# pl2303HXD.net
KiCad netlist of a schematic drawn in Altium Designer
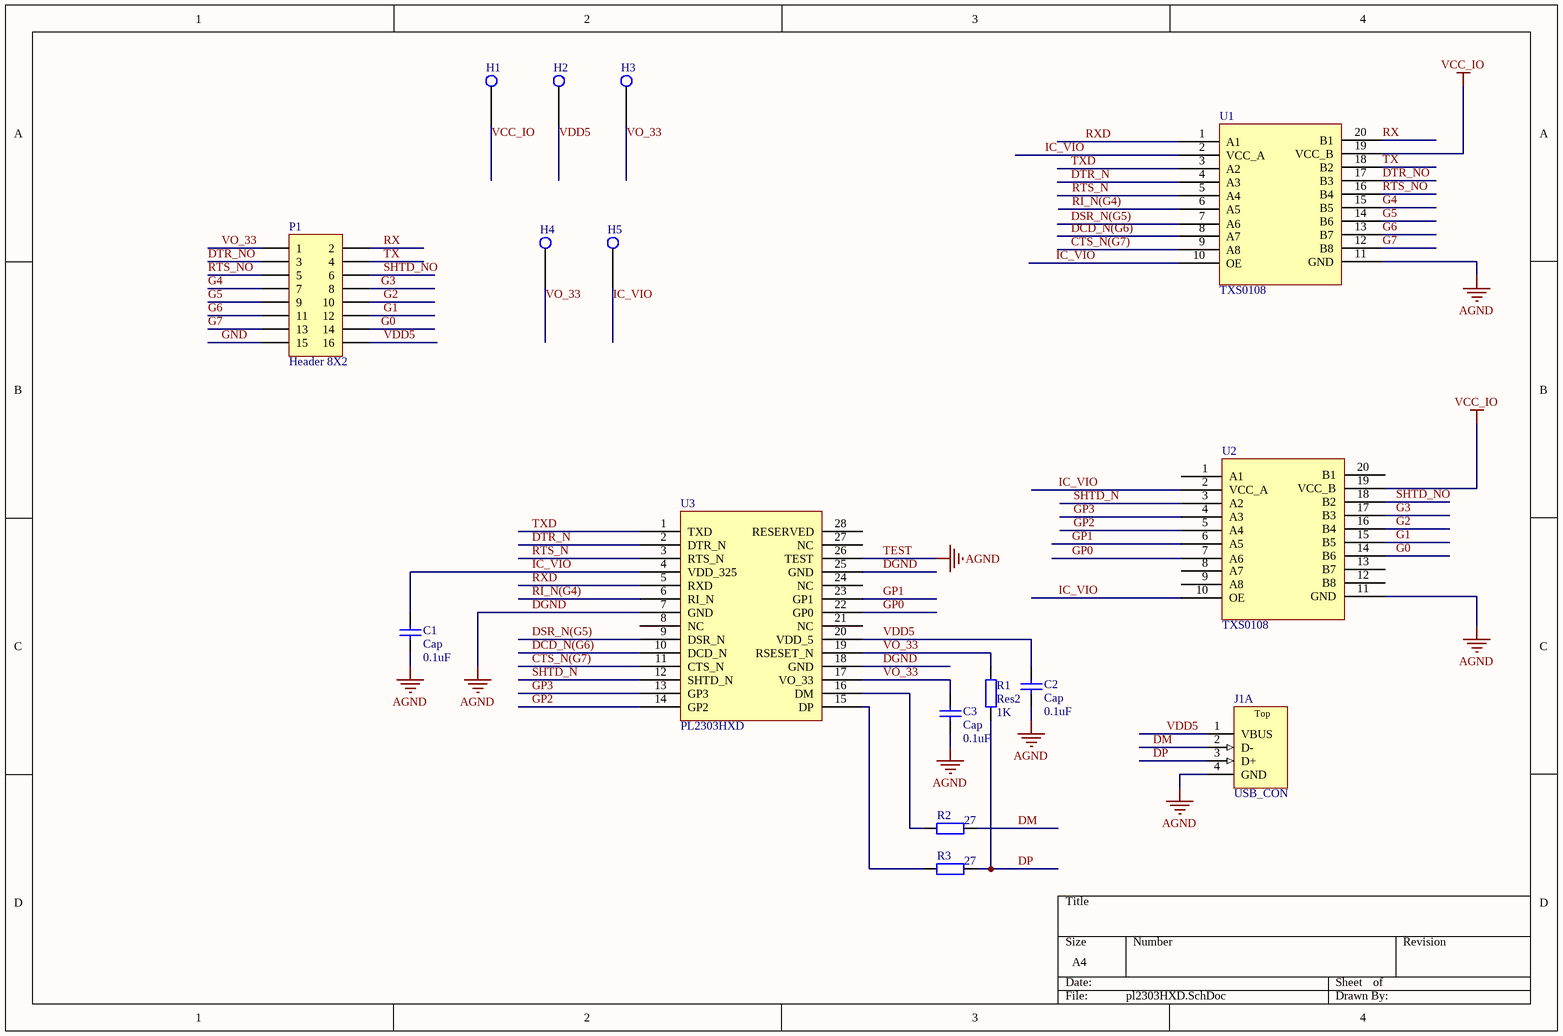
[diagram p0: pl2303HXD.SchDoc]

(export (version "E")
  (design (tool "Eeschema 10.0.6"))
  (components
    (comp (ref "C1")
      (value "Cap")
      (footprint "CAP-0603")
      (description "Capacitor")
      (fields (field (name "ALTIUM_VALUE") "0.1uF") (field (name "PUBLISHER") "Altium Limited"))
      (libsource (lib "Miscellaneous Devices") (part "Cap"))
    )
    (comp (ref "C2")
      (value "Cap")
      (footprint "CAP-0603")
      (description "Capacitor")
      (fields (field (name "ALTIUM_VALUE") "0.1uF") (field (name "PUBLISHER") "Altium Limited"))
      (libsource (lib "Miscellaneous Devices") (part "Cap"))
    )
    (comp (ref "C3")
      (value "Cap")
      (footprint "CAP-0603")
      (description "Capacitor")
      (fields (field (name "ALTIUM_VALUE") "0.1uF") (field (name "PUBLISHER") "Altium Limited"))
      (libsource (lib "Miscellaneous Devices") (part "Cap"))
    )
    (comp (ref "H1") (value "Header 1") (footprint "HDR1*1") (libsource (lib "MLI") (part "Header 1")))
    (comp (ref "H2") (value "Header 1") (footprint "HDR1*1") (libsource (lib "MLI") (part "Header 1")))
    (comp (ref "H3") (value "Header 1") (footprint "HDR1*1") (libsource (lib "MLI") (part "Header 1")))
    (comp (ref "H4") (value "Header 1") (footprint "HDR1*1") (libsource (lib "MLI") (part "Header 1")))
    (comp (ref "H5") (value "Header 1") (footprint "HDR1*1") (libsource (lib "MLI") (part "Header 1")))
    (comp (ref "J1")
      (value "USB_CON")
      (footprint "USB-A")
      (description "USB 1.1, Right Angle, Thru-Hole, A Type, Receptacle, 4x4x4x4 Position, Fourfold Stacked, Black")
      (fields (field (name "PUBLISHER") "Altium Limited"))
      (libsource (lib "SkyWorks2") (part "USBx4"))
    )
    (comp (ref "P1")
      (value "Header 8X2")
      (footprint "HDR2*8")
      (description "Header, 8-Pin, Dual row")
      (fields (field (name "PUBLISHER") "Altium Limited"))
      (libsource (lib "Miscellaneous Connectors") (part "Header 8X2"))
    )
    (comp (ref "R1")
      (value "Res2")
      (footprint "RES-0603")
      (description "Resistor")
      (fields (field (name "ALTIUM_VALUE") "1K") (field (name "PUBLISHER") "Altium Limited"))
      (libsource (lib "Miscellaneous Devices") (part "Res2"))
    )
    (comp (ref "R2")
      (value "27")
      (footprint "RES-0603")
      (description "Resistor")
      (fields (field (name "Comment") "Res2") (field (name "PUBLISHER") "Altium Limited"))
      (libsource (lib "") (part "Res2_1"))
    )
    (comp (ref "R3")
      (value "27")
      (footprint "RES-0603")
      (description "Resistor")
      (fields (field (name "Comment") "Res2") (field (name "PUBLISHER") "Altium Limited"))
      (libsource (lib "") (part "Res2_1"))
    )
    (comp (ref "U1")
      (value "TXS0108")
      (footprint "TSSOP20_44MM_065P")
      (libsource (lib "MLI") (part "TXS0108"))
    )
    (comp (ref "U2")
      (value "TXS0108")
      (footprint "TSSOP20_44MM_065P")
      (libsource (lib "MLI") (part "TXS0108"))
    )
    (comp (ref "U3") (value "PL2303HXD") (footprint "SSOP28") (libsource (lib "MLI") (part "PL2303HXD")))
  )
  (nets
    (net (code "1") (name "/CTS_N(G7)") (class "Default")
      (node (ref "U1") (pin "9") (pinfunction "A8_9") (pintype "passive"))
      (node (ref "U3") (pin "11") (pinfunction "CTS_N_11") (pintype "passive"))
    )
    (net (code "2") (name "/DCD_N(G6)") (class "Default")
      (node (ref "U1") (pin "8") (pinfunction "A7_8") (pintype "passive"))
      (node (ref "U3") (pin "10") (pinfunction "DCD_N_10") (pintype "passive"))
    )
    (net (code "3") (name "/DM") (class "Default")
      (node (ref "J1") (pin "2") (pinfunction "D-_2") (pintype "input"))
      (node (ref "R2") (pin "2") (pinfunction "2_2") (pintype "passive"))
    )
    (net (code "4") (name "/DP") (class "Default")
      (node (ref "J1") (pin "3") (pinfunction "D+_3") (pintype "input"))
      (node (ref "R1") (pin "1") (pinfunction "1_1") (pintype "passive"))
      (node (ref "R3") (pin "2") (pinfunction "2_2") (pintype "passive"))
    )
    (net (code "5") (name "/DSR_N(G5)") (class "Default")
      (node (ref "U1") (pin "7") (pinfunction "A6_7") (pintype "passive"))
      (node (ref "U3") (pin "9") (pinfunction "DSR_N_9") (pintype "passive"))
    )
    (net (code "6") (name "/DTR_N") (class "Default")
      (node (ref "U1") (pin "4") (pinfunction "A3_4") (pintype "passive"))
      (node (ref "U3") (pin "2") (pinfunction "DTR_N_2") (pintype "passive"))
    )
    (net (code "7") (name "/DTR_NO") (class "Default")
      (node (ref "P1") (pin "3") (pinfunction "3_3") (pintype "passive"))
      (node (ref "U1") (pin "17") (pinfunction "B3_17") (pintype "passive"))
    )
    (net (code "8") (name "/G0") (class "Default")
      (node (ref "P1") (pin "14") (pinfunction "14_14") (pintype "passive"))
      (node (ref "U2") (pin "14") (pinfunction "B6_14") (pintype "passive"))
    )
    (net (code "9") (name "/G1") (class "Default")
      (node (ref "P1") (pin "12") (pinfunction "12_12") (pintype "passive"))
      (node (ref "U2") (pin "15") (pinfunction "B5_15") (pintype "passive"))
    )
    (net (code "10") (name "/G2") (class "Default")
      (node (ref "P1") (pin "10") (pinfunction "10_10") (pintype "passive"))
      (node (ref "U2") (pin "16") (pinfunction "B4_16") (pintype "passive"))
    )
    (net (code "11") (name "/G3") (class "Default")
      (node (ref "P1") (pin "8") (pinfunction "8_8") (pintype "passive"))
      (node (ref "U2") (pin "17") (pinfunction "B3_17") (pintype "passive"))
    )
    (net (code "12") (name "/G4") (class "Default")
      (node (ref "P1") (pin "7") (pinfunction "7_7") (pintype "passive"))
      (node (ref "U1") (pin "15") (pinfunction "B5_15") (pintype "passive"))
    )
    (net (code "13") (name "/G5") (class "Default")
      (node (ref "P1") (pin "9") (pinfunction "9_9") (pintype "passive"))
      (node (ref "U1") (pin "14") (pinfunction "B6_14") (pintype "passive"))
    )
    (net (code "14") (name "/G6") (class "Default")
      (node (ref "P1") (pin "11") (pinfunction "11_11") (pintype "passive"))
      (node (ref "U1") (pin "13") (pinfunction "B7_13") (pintype "passive"))
    )
    (net (code "15") (name "/G7") (class "Default")
      (node (ref "P1") (pin "13") (pinfunction "13_13") (pintype "passive"))
      (node (ref "U1") (pin "12") (pinfunction "B8_12") (pintype "passive"))
    )
    (net (code "16") (name "/GND") (class "Default")
      (node (ref "P1") (pin "15") (pinfunction "15_15") (pintype "passive"))
    )
    (net (code "17") (name "/GP0") (class "Default")
      (node (ref "U2") (pin "7") (pinfunction "A6_7") (pintype "passive"))
      (node (ref "U3") (pin "22") (pinfunction "GP0_22") (pintype "passive"))
    )
    (net (code "18") (name "/GP1") (class "Default")
      (node (ref "U2") (pin "6") (pinfunction "A5_6") (pintype "passive"))
      (node (ref "U3") (pin "23") (pinfunction "GP1_23") (pintype "passive"))
    )
    (net (code "19") (name "/GP2") (class "Default")
      (node (ref "U2") (pin "5") (pinfunction "A4_5") (pintype "passive"))
      (node (ref "U3") (pin "14") (pinfunction "GP2_14") (pintype "passive"))
    )
    (net (code "20") (name "/GP3") (class "Default")
      (node (ref "U2") (pin "4") (pinfunction "A3_4") (pintype "passive"))
      (node (ref "U3") (pin "13") (pinfunction "GP3_13") (pintype "passive"))
    )
    (net (code "21") (name "/IC_VIO") (class "Default")
      (node (ref "C1") (pin "1") (pinfunction "1_1") (pintype "passive"))
      (node (ref "H5") (pin "1") (pinfunction "p_1") (pintype "passive"))
      (node (ref "U1") (pin "10") (pinfunction "OE_10") (pintype "passive"))
      (node (ref "U1") (pin "2") (pinfunction "VCC_A_2") (pintype "passive"))
      (node (ref "U2") (pin "10") (pinfunction "OE_10") (pintype "passive"))
      (node (ref "U2") (pin "2") (pinfunction "VCC_A_2") (pintype "passive"))
      (node (ref "U3") (pin "4") (pinfunction "VDD_325_4") (pintype "passive"))
    )
    (net (code "22") (name "/RI_N(G4)") (class "Default")
      (node (ref "U1") (pin "6") (pinfunction "A5_6") (pintype "passive"))
      (node (ref "U3") (pin "6") (pinfunction "RI_N_6") (pintype "passive"))
    )
    (net (code "23") (name "/RTS_N") (class "Default")
      (node (ref "U1") (pin "5") (pinfunction "A4_5") (pintype "passive"))
      (node (ref "U3") (pin "3") (pinfunction "RTS_N_3") (pintype "passive"))
    )
    (net (code "24") (name "/RTS_NO") (class "Default")
      (node (ref "P1") (pin "5") (pinfunction "5_5") (pintype "passive"))
      (node (ref "U1") (pin "16") (pinfunction "B4_16") (pintype "passive"))
    )
    (net (code "25") (name "/RX") (class "Default")
      (node (ref "P1") (pin "2") (pinfunction "2_2") (pintype "passive"))
      (node (ref "U1") (pin "20") (pinfunction "B1_20") (pintype "passive"))
    )
    (net (code "26") (name "/RXD") (class "Default")
      (node (ref "U1") (pin "1") (pinfunction "A1_1") (pintype "passive"))
      (node (ref "U3") (pin "5") (pinfunction "RXD_5") (pintype "passive"))
    )
    (net (code "27") (name "/SHTD_N") (class "Default")
      (node (ref "U2") (pin "3") (pinfunction "A2_3") (pintype "passive"))
      (node (ref "U3") (pin "12") (pinfunction "SHTD_N_12") (pintype "passive"))
    )
    (net (code "28") (name "/SHTD_NO") (class "Default")
      (node (ref "P1") (pin "6") (pinfunction "6_6") (pintype "passive"))
      (node (ref "U2") (pin "18") (pinfunction "B2_18") (pintype "passive"))
    )
    (net (code "29") (name "/TX") (class "Default")
      (node (ref "P1") (pin "4") (pinfunction "4_4") (pintype "passive"))
      (node (ref "U1") (pin "18") (pinfunction "B2_18") (pintype "passive"))
    )
    (net (code "30") (name "/TXD") (class "Default")
      (node (ref "U1") (pin "3") (pinfunction "A2_3") (pintype "passive"))
      (node (ref "U3") (pin "1") (pinfunction "TXD_1") (pintype "passive"))
    )
    (net (code "31") (name "/VDD5") (class "Default")
      (node (ref "C2") (pin "1") (pinfunction "1_1") (pintype "passive"))
      (node (ref "H2") (pin "1") (pinfunction "p_1") (pintype "passive"))
      (node (ref "J1") (pin "1") (pinfunction "VBUS_1") (pintype "power_in"))
      (node (ref "P1") (pin "16") (pinfunction "16_16") (pintype "passive"))
      (node (ref "U3") (pin "20") (pinfunction "VDD_5_20") (pintype "passive"))
    )
    (net (code "32") (name "/VO_33") (class "Default")
      (node (ref "C3") (pin "1") (pinfunction "1_1") (pintype "passive"))
      (node (ref "H3") (pin "1") (pinfunction "p_1") (pintype "passive"))
      (node (ref "H4") (pin "1") (pinfunction "p_1") (pintype "passive"))
      (node (ref "P1") (pin "1") (pinfunction "1_1") (pintype "passive"))
      (node (ref "R1") (pin "2") (pinfunction "2_2") (pintype "passive"))
      (node (ref "U3") (pin "17") (pinfunction "VO_33_17") (pintype "passive"))
      (node (ref "U3") (pin "19") (pinfunction "RSESET_N_19") (pintype "passive"))
    )
    (net (code "33") (name "AGND") (class "Default")
      (node (ref "C1") (pin "2") (pinfunction "2_2") (pintype "passive"))
      (node (ref "C2") (pin "2") (pinfunction "2_2") (pintype "passive"))
      (node (ref "C3") (pin "2") (pinfunction "2_2") (pintype "passive"))
      (node (ref "J1") (pin "4") (pinfunction "GND_4") (pintype "power_in"))
      (node (ref "U1") (pin "11") (pinfunction "GND_11") (pintype "passive"))
      (node (ref "U2") (pin "11") (pinfunction "GND_11") (pintype "passive"))
      (node (ref "U3") (pin "18") (pinfunction "GND_18") (pintype "passive"))
      (node (ref "U3") (pin "25") (pinfunction "GND_25") (pintype "passive"))
      (node (ref "U3") (pin "26") (pinfunction "TEST_26") (pintype "passive"))
      (node (ref "U3") (pin "7") (pinfunction "GND_7") (pintype "passive"))
    )
    (net (code "34") (name "Net-(U3-DM)") (class "Default")
      (node (ref "R2") (pin "1") (pinfunction "1_1") (pintype "passive"))
      (node (ref "U3") (pin "16") (pinfunction "DM_16") (pintype "passive"))
    )
    (net (code "35") (name "Net-(U3-DP)") (class "Default")
      (node (ref "R3") (pin "1") (pinfunction "1_1") (pintype "passive"))
      (node (ref "U3") (pin "15") (pinfunction "DP_15") (pintype "passive"))
    )
    (net (code "36") (name "VCC_IO") (class "Default")
      (node (ref "H1") (pin "1") (pinfunction "p_1") (pintype "passive"))
      (node (ref "U1") (pin "19") (pinfunction "VCC_B_19") (pintype "passive"))
      (node (ref "U2") (pin "19") (pinfunction "VCC_B_19") (pintype "passive"))
    )
    (net (code "37") (name "unconnected-(U2-A1-Pad1)") (class "Default")
      (node (ref "U2") (pin "1") (pinfunction "A1_1") (pintype "passive"))
    )
    (net (code "38") (name "unconnected-(U2-A7-Pad8)") (class "Default")
      (node (ref "U2") (pin "8") (pinfunction "A7_8") (pintype "passive"))
    )
    (net (code "39") (name "unconnected-(U2-A8-Pad9)") (class "Default")
      (node (ref "U2") (pin "9") (pinfunction "A8_9") (pintype "passive"))
    )
    (net (code "40") (name "unconnected-(U2-B1-Pad20)") (class "Default")
      (node (ref "U2") (pin "20") (pinfunction "B1_20") (pintype "passive"))
    )
    (net (code "41") (name "unconnected-(U2-B7-Pad13)") (class "Default")
      (node (ref "U2") (pin "13") (pinfunction "B7_13") (pintype "passive"))
    )
    (net (code "42") (name "unconnected-(U2-B8-Pad12)") (class "Default")
      (node (ref "U2") (pin "12") (pinfunction "B8_12") (pintype "passive"))
    )
    (net (code "43") (name "unconnected-(U3-NC-Pad8)") (class "Default")
      (node (ref "U3") (pin "8") (pinfunction "NC_8") (pintype "passive"))
    )
    (net (code "44") (name "unconnected-(U3-NC-Pad21)") (class "Default")
      (node (ref "U3") (pin "21") (pinfunction "NC_21") (pintype "passive"))
    )
    (net (code "45") (name "unconnected-(U3-NC-Pad24)") (class "Default")
      (node (ref "U3") (pin "24") (pinfunction "NC_24") (pintype "passive"))
    )
    (net (code "46") (name "unconnected-(U3-NC-Pad27)") (class "Default")
      (node (ref "U3") (pin "27") (pinfunction "NC_27") (pintype "passive"))
    )
    (net (code "47") (name "unconnected-(U3-RESERVED-Pad28)") (class "Default")
      (node (ref "U3") (pin "28") (pinfunction "RESERVED_28") (pintype "passive"))
    )
  )
)
